# Conectores.net
KiCad netlist of a schematic drawn in Altium Designer
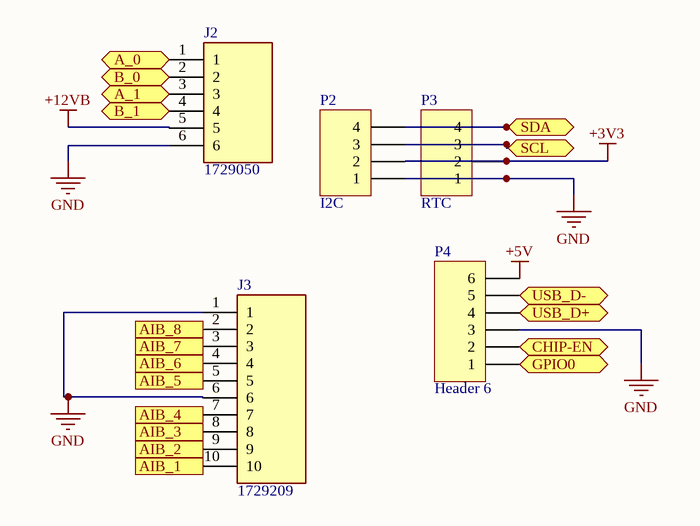
[diagram p0: Conectores.SchDoc]

(export (version "E")
  (design (tool "Eeschema 10.0.6"))
  (components
    (comp (ref "J2")
      (value "1729050")
      (footprint "1729050")
      (description "Connector")
      (fields (field (name "MOUSER PART NUMBER") "651-1729050"))
      (libsource (lib "CPU FPS-400 2022") (part "1729050"))
    )
    (comp (ref "J3")
      (value "1729209")
      (footprint "SamacSys:1729209")
      (description "Connector")
      (fields (field (name "MOUSER PART NUMBER") "651-1729209"))
      (libsource (lib "*") (part "1729209"))
    )
    (comp (ref "P2")
      (value "I2C")
      (footprint "HDR1X4")
      (description "Header, 4-Pin")
      (fields (field (name "PUBLISHER") "Altium Limited"))
      (libsource (lib "Miscellaneous Connectors") (part "Header 4"))
    )
    (comp (ref "P3")
      (value "RTC")
      (footprint "HDR1X4")
      (description "Header, 4-Pin")
      (fields (field (name "PUBLISHER") "Altium Limited"))
      (libsource (lib "Miscellaneous Connectors") (part "Header 4"))
    )
    (comp (ref "P4")
      (value "Header 6")
      (footprint "HDR1X6")
      (description "Header, 6-Pin")
      (fields (field (name "PUBLISHER") "Altium Limited"))
      (libsource (lib "Miscellaneous Connectors") (part "Header 6"))
    )
  )
  (nets
    (net (code "1") (name "+3V3") (class "Default")
      (node (ref "P2") (pin "2") (pinfunction "2_2") (pintype "passive"))
      (node (ref "P3") (pin "2") (pinfunction "2_2") (pintype "passive"))
    )
    (net (code "2") (name "+5V") (class "Default")
      (node (ref "P4") (pin "6") (pinfunction "6_6") (pintype "passive"))
    )
    (net (code "3") (name "+12VB") (class "Default")
      (node (ref "J2") (pin "5") (pinfunction "5_5") (pintype "passive"))
    )
    (net (code "4") (name "/AIB_1") (class "Default")
      (node (ref "J3") (pin "10") (pinfunction "10_10") (pintype "passive"))
    )
    (net (code "5") (name "/AIB_2") (class "Default")
      (node (ref "J3") (pin "9") (pinfunction "9_9") (pintype "passive"))
    )
    (net (code "6") (name "/AIB_3") (class "Default")
      (node (ref "J3") (pin "8") (pinfunction "8_8") (pintype "passive"))
    )
    (net (code "7") (name "/AIB_4") (class "Default")
      (node (ref "J3") (pin "7") (pinfunction "7_7") (pintype "passive"))
    )
    (net (code "8") (name "/AIB_5") (class "Default")
      (node (ref "J3") (pin "5") (pinfunction "5_5") (pintype "passive"))
    )
    (net (code "9") (name "/AIB_6") (class "Default")
      (node (ref "J3") (pin "4") (pinfunction "4_4") (pintype "passive"))
    )
    (net (code "10") (name "/AIB_7") (class "Default")
      (node (ref "J3") (pin "3") (pinfunction "3_3") (pintype "passive"))
    )
    (net (code "11") (name "/AIB_8") (class "Default")
      (node (ref "J3") (pin "2") (pinfunction "2_2") (pintype "passive"))
    )
    (net (code "12") (name "/A_0") (class "Default")
      (node (ref "J2") (pin "1") (pinfunction "1_1") (pintype "passive"))
    )
    (net (code "13") (name "/A_1") (class "Default")
      (node (ref "J2") (pin "3") (pinfunction "3_3") (pintype "passive"))
    )
    (net (code "14") (name "/B_0") (class "Default")
      (node (ref "J2") (pin "2") (pinfunction "2_2") (pintype "passive"))
    )
    (net (code "15") (name "/B_1") (class "Default")
      (node (ref "J2") (pin "4") (pinfunction "4_4") (pintype "passive"))
    )
    (net (code "16") (name "/CHIP-EN") (class "Default")
      (node (ref "P4") (pin "2") (pinfunction "2_2") (pintype "passive"))
    )
    (net (code "17") (name "/GPIO0") (class "Default")
      (node (ref "P4") (pin "1") (pinfunction "1_1") (pintype "passive"))
    )
    (net (code "18") (name "/SCL") (class "Default")
      (node (ref "P2") (pin "3") (pinfunction "3_3") (pintype "passive"))
      (node (ref "P3") (pin "3") (pinfunction "3_3") (pintype "passive"))
    )
    (net (code "19") (name "/SDA") (class "Default")
      (node (ref "P2") (pin "4") (pinfunction "4_4") (pintype "passive"))
      (node (ref "P3") (pin "4") (pinfunction "4_4") (pintype "passive"))
    )
    (net (code "20") (name "/USB_D+") (class "Default")
      (node (ref "P4") (pin "4") (pinfunction "4_4") (pintype "passive"))
    )
    (net (code "21") (name "/USB_D-") (class "Default")
      (node (ref "P4") (pin "5") (pinfunction "5_5") (pintype "passive"))
    )
    (net (code "22") (name "GND") (class "Default")
      (node (ref "J2") (pin "6") (pinfunction "6_6") (pintype "passive"))
      (node (ref "J3") (pin "1") (pinfunction "1_1") (pintype "passive"))
      (node (ref "J3") (pin "6") (pinfunction "6_6") (pintype "passive"))
      (node (ref "P2") (pin "1") (pinfunction "1_1") (pintype "passive"))
      (node (ref "P3") (pin "1") (pinfunction "1_1") (pintype "passive"))
      (node (ref "P4") (pin "3") (pinfunction "3_3") (pintype "passive"))
    )
  )
)
